# RK3399_EMMC_ADC_PCIE.net
KiCad netlist of a schematic drawn in Altium Designer
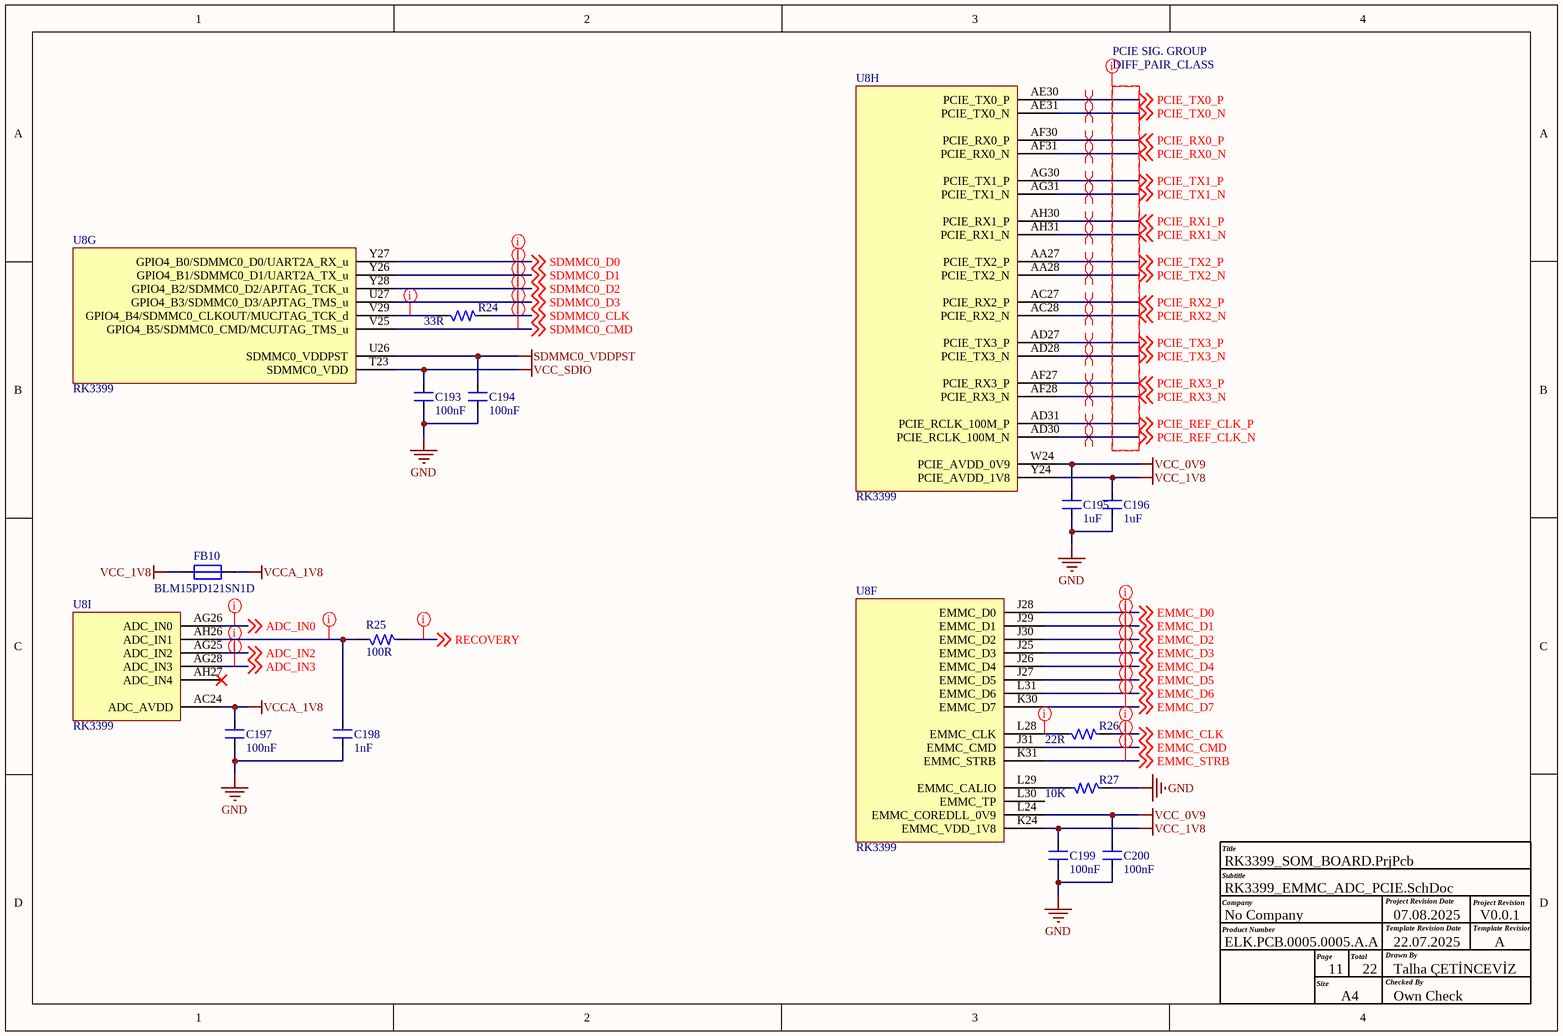
[diagram p0: RK3399_EMMC_ADC_PCIE.SchDoc]

(export (version "E")
  (design (tool "Eeschema 10.0.6"))
  (components
    (comp (ref "C193")
      (value "100nF")
      (footprint "CAP_0201")
      (description "0.1µF ±10% 25V Ceramic Capacitor X5R 0201 (0603 Metric)")
      (fields
        (field (name "MANUFACTURER") "TDK Corporation")
        (field (name "MANUFACTURER PART NUMBER") "C0603X5R1E104K030BB")
      )
      (libsource (lib "EsteemPCB_SOM_Course_intlib") (part "CAP_100nF-25V-10%-0201"))
    )
    (comp (ref "C194")
      (value "100nF")
      (footprint "CAP_0201")
      (description "0.1µF ±10% 25V Ceramic Capacitor X5R 0201 (0603 Metric)")
      (fields
        (field (name "MANUFACTURER") "TDK Corporation")
        (field (name "MANUFACTURER PART NUMBER") "C0603X5R1E104K030BB")
      )
      (libsource (lib "EsteemPCB_SOM_Course_intlib") (part "CAP_100nF-25V-10%-0201"))
    )
    (comp (ref "C195")
      (value "1uF")
      (footprint "CAP_0201")
      (description "1µF ±20% 16V Ceramic Capacitor X5R 0201 (0603 Metric)")
      (fields
        (field (name "MANUFACTURER") "Samsung Electro-Mechanics")
        (field (name "MANUFACTURER PART NUMBER") "CL03A105MO3NRNH")
      )
      (libsource (lib "EsteemPCB_SOM_Course_intlib") (part "CAP_1uF-16V-10%-0201"))
    )
    (comp (ref "C196")
      (value "1uF")
      (footprint "CAP_0201")
      (description "1µF ±20% 16V Ceramic Capacitor X5R 0201 (0603 Metric)")
      (fields
        (field (name "MANUFACTURER") "Samsung Electro-Mechanics")
        (field (name "MANUFACTURER PART NUMBER") "CL03A105MO3NRNH")
      )
      (libsource (lib "EsteemPCB_SOM_Course_intlib") (part "CAP_1uF-16V-10%-0201"))
    )
    (comp (ref "C197")
      (value "100nF")
      (footprint "CAP_0201")
      (description "0.1µF ±10% 25V Ceramic Capacitor X5R 0201 (0603 Metric)")
      (fields
        (field (name "MANUFACTURER") "TDK Corporation")
        (field (name "MANUFACTURER PART NUMBER") "C0603X5R1E104K030BB")
      )
      (libsource (lib "EsteemPCB_SOM_Course_intlib") (part "CAP_100nF-25V-10%-0201"))
    )
    (comp (ref "C198")
      (value "1nF")
      (footprint "CAP_0201")
      (description "1000pF ±10% 16V Ceramic Capacitor X7R 0201 (0603 Metric)")
      (fields
        (field (name "MANUFACTURER") "Murata Electronics")
        (field (name "MANUFACTURER PART NUMBER") "GRM033R71C102KA01D")
      )
      (libsource (lib "EsteemPCB_SOM_Course_intlib") (part "CAP_1nF-16V-10%-0201"))
    )
    (comp (ref "C199")
      (value "100nF")
      (footprint "CAP_0201")
      (description "0.1µF ±10% 25V Ceramic Capacitor X5R 0201 (0603 Metric)")
      (fields
        (field (name "MANUFACTURER") "TDK Corporation")
        (field (name "MANUFACTURER PART NUMBER") "C0603X5R1E104K030BB")
      )
      (libsource (lib "EsteemPCB_SOM_Course_intlib") (part "CAP_100nF-25V-10%-0201"))
    )
    (comp (ref "C200")
      (value "100nF")
      (footprint "CAP_0201")
      (description "0.1µF ±10% 25V Ceramic Capacitor X5R 0201 (0603 Metric)")
      (fields
        (field (name "MANUFACTURER") "TDK Corporation")
        (field (name "MANUFACTURER PART NUMBER") "C0603X5R1E104K030BB")
      )
      (libsource (lib "EsteemPCB_SOM_Course_intlib") (part "CAP_100nF-25V-10%-0201"))
    )
    (comp (ref "FB10")
      (value "BLM15PD121SN1D")
      (footprint "RES_0402")
      (description "120 Ohms @ 100MHz 1 Power Line Ferrite Bead 0402 (1005 Metric) 1.3A 90mOhm")
      (fields (field (name "MANUFACTURER") "Murata Electronics"))
      (libsource (lib "EsteemPCB_SOM_Course_intlib") (part "FB_120R-1.3A-100Mhz-0402"))
    )
    (comp (ref "R24")
      (value "33R")
      (footprint "RES_0201")
      (description "33 Ohms ±1% 0.05W, 1/20W Chip Resistor 0201 (0603 Metric) Thick Film")
      (fields
        (field (name "MANUFACTURER") "Yageo")
        (field (name "MANUFACTURER PART NUMBER") "RC0201FR-0733RL")
      )
      (libsource (lib "EsteemPCB_SOM_Course_intlib") (part "RES_33R-0.05W-1%-0201"))
    )
    (comp (ref "R25")
      (value "100R")
      (footprint "RES_0201")
      (description "100 kOhms ±1% 0.05W, 1/20W Chip Resistor 0201 (0603 Metric) Automotive AEC-Q200 Thick Film")
      (fields
        (field (name "MANUFACTURER") "Panasonic Electronic Components")
        (field (name "MANUFACTURER PART NUMBER") "ERJ-1GNF1003C")
      )
      (libsource (lib "EsteemPCB_SOM_Course_intlib") (part "RES_100R-0.05W-1%-0201"))
    )
    (comp (ref "R26")
      (value "22R")
      (footprint "RES_0201")
      (description "22 Ohms ±1% 0.05W, 1/20W Chip Resistor 0201 (0603 Metric) Moisture Resistant Thick Film")
      (fields
        (field (name "MANUFACTURER") "Yageo")
        (field (name "MANUFACTURER PART NUMBER") "RC0201FR-0722RL")
      )
      (libsource (lib "EsteemPCB_SOM_Course_intlib") (part "RES_22R-0.05W-1%-0201"))
    )
    (comp (ref "R27")
      (value "10K")
      (footprint "RES_0201")
      (description "10 kOhms ±1% 0.05W, 1/20W Chip Resistor 0201 (0603 Metric) Thick Film")
      (fields
        (field (name "MANUFACTURER") "Stackpole Electronics Inc")
        (field (name "MANUFACTURER PART NUMBER") "RMCF0201FT10K0")
      )
      (libsource (lib "EsteemPCB_SOM_Course_intlib") (part "RES_10K-0.05W-1%-0201"))
    )
    (comp (ref "U8")
      (value "RK3399")
      (footprint "FBGA828_23_826X826")
      (description "RK3399 is a low power, high performance processor for computing, personal mobile.")
      (fields (field (name "MANUFACTURER") "Rockchip"))
      (libsource (lib "EsteemPCB_SOM_Course_intlib") (part "IC_RK3399-FCBGA828"))
    )
  )
  (nets
    (net (code "1") (name "ADC_IN0") (class "Default")
      (node (ref "U8") (pin "AG26") (pinfunction "ADC_IN0_AG26") (pintype "passive"))
    )
    (net (code "2") (name "ADC_IN2") (class "Default")
      (node (ref "U8") (pin "AG25") (pinfunction "ADC_IN2_AG25") (pintype "passive"))
    )
    (net (code "3") (name "ADC_IN3") (class "Default")
      (node (ref "U8") (pin "AG28") (pinfunction "ADC_IN3_AG28") (pintype "passive"))
    )
    (net (code "4") (name "EMMC_CLK") (class "Default")
      (node (ref "R26") (pin "2") (pinfunction "2_2") (pintype "passive"))
    )
    (net (code "5") (name "EMMC_CMD") (class "Default")
      (node (ref "U8") (pin "J31") (pinfunction "EMMC_CMD_J31") (pintype "passive"))
    )
    (net (code "6") (name "EMMC_D0") (class "Default")
      (node (ref "U8") (pin "J28") (pinfunction "EMMC_D0_J28") (pintype "passive"))
    )
    (net (code "7") (name "EMMC_D1") (class "Default")
      (node (ref "U8") (pin "J29") (pinfunction "EMMC_D1_J29") (pintype "passive"))
    )
    (net (code "8") (name "EMMC_D2") (class "Default")
      (node (ref "U8") (pin "J30") (pinfunction "EMMC_D2_J30") (pintype "passive"))
    )
    (net (code "9") (name "EMMC_D3") (class "Default")
      (node (ref "U8") (pin "J25") (pinfunction "EMMC_D3_J25") (pintype "passive"))
    )
    (net (code "10") (name "EMMC_D4") (class "Default")
      (node (ref "U8") (pin "J26") (pinfunction "EMMC_D4_J26") (pintype "passive"))
    )
    (net (code "11") (name "EMMC_D5") (class "Default")
      (node (ref "U8") (pin "J27") (pinfunction "EMMC_D5_J27") (pintype "passive"))
    )
    (net (code "12") (name "EMMC_D6") (class "Default")
      (node (ref "U8") (pin "L31") (pinfunction "EMMC_D6_L31") (pintype "passive"))
    )
    (net (code "13") (name "EMMC_D7") (class "Default")
      (node (ref "U8") (pin "K30") (pinfunction "EMMC_D7_K30") (pintype "passive"))
    )
    (net (code "14") (name "EMMC_STRB") (class "Default")
      (node (ref "U8") (pin "K31") (pinfunction "EMMC_STRB_K31") (pintype "passive"))
    )
    (net (code "15") (name "GND") (class "Default")
      (node (ref "C193") (pin "1") (pinfunction "1_1") (pintype "passive"))
      (node (ref "C194") (pin "1") (pinfunction "1_1") (pintype "passive"))
      (node (ref "C195") (pin "1") (pinfunction "1_1") (pintype "passive"))
      (node (ref "C196") (pin "1") (pinfunction "1_1") (pintype "passive"))
      (node (ref "C197") (pin "1") (pinfunction "1_1") (pintype "passive"))
      (node (ref "C198") (pin "1") (pinfunction "1_1") (pintype "passive"))
      (node (ref "C199") (pin "1") (pinfunction "1_1") (pintype "passive"))
      (node (ref "C200") (pin "1") (pinfunction "1_1") (pintype "passive"))
      (node (ref "R27") (pin "1") (pinfunction "1_1") (pintype "passive"))
    )
    (net (code "16") (name "Net-(U8F-EMMC_CALIO)") (class "Default")
      (node (ref "R27") (pin "2") (pinfunction "2_2") (pintype "passive"))
      (node (ref "U8") (pin "L29") (pinfunction "EMMC_CALIO_L29") (pintype "passive"))
    )
    (net (code "17") (name "Net-(U8F-EMMC_CLK)") (class "Default")
      (node (ref "R26") (pin "1") (pinfunction "1_1") (pintype "passive"))
      (node (ref "U8") (pin "L28") (pinfunction "EMMC_CLK_L28") (pintype "passive"))
    )
    (net (code "18") (name "Net-(U8G-GPIO4_B4{slash}SDMMC0_CLKOUT{slash}MUCJTAG_TCK_d)") (class "Default")
      (node (ref "R24") (pin "1") (pinfunction "1_1") (pintype "passive"))
      (node (ref "U8") (pin "V29") (pinfunction "GPIO4_B4/SDMMC0_CLKOUT/MUCJTAG_TCK_d_V29") (pintype "passive"))
    )
    (net (code "19") (name "Net-(U8I-ADC_IN1)") (class "Default")
      (node (ref "C198") (pin "2") (pinfunction "2_2") (pintype "passive"))
      (node (ref "R25") (pin "1") (pinfunction "1_1") (pintype "passive"))
      (node (ref "U8") (pin "AH26") (pinfunction "ADC_IN1_AH26") (pintype "passive"))
    )
    (net (code "20") (name "PCIE_REF_CLK_N") (class "Default")
      (node (ref "U8") (pin "AD30") (pinfunction "PCIE_RCLK_100M_N_AD30") (pintype "passive"))
    )
    (net (code "21") (name "PCIE_REF_CLK_P") (class "Default")
      (node (ref "U8") (pin "AD31") (pinfunction "PCIE_RCLK_100M_P_AD31") (pintype "passive"))
    )
    (net (code "22") (name "PCIE_RX0_N") (class "Default")
      (node (ref "U8") (pin "AF31") (pinfunction "PCIE_RX0_N_AF31") (pintype "passive"))
    )
    (net (code "23") (name "PCIE_RX0_P") (class "Default")
      (node (ref "U8") (pin "AF30") (pinfunction "PCIE_RX0_P_AF30") (pintype "passive"))
    )
    (net (code "24") (name "PCIE_RX1_N") (class "Default")
      (node (ref "U8") (pin "AH31") (pinfunction "PCIE_RX1_N_AH31") (pintype "passive"))
    )
    (net (code "25") (name "PCIE_RX1_P") (class "Default")
      (node (ref "U8") (pin "AH30") (pinfunction "PCIE_RX1_P_AH30") (pintype "passive"))
    )
    (net (code "26") (name "PCIE_RX2_N") (class "Default")
      (node (ref "U8") (pin "AC28") (pinfunction "PCIE_RX2_N_AC28") (pintype "passive"))
    )
    (net (code "27") (name "PCIE_RX2_P") (class "Default")
      (node (ref "U8") (pin "AC27") (pinfunction "PCIE_RX2_P_AC27") (pintype "passive"))
    )
    (net (code "28") (name "PCIE_RX3_N") (class "Default")
      (node (ref "U8") (pin "AF28") (pinfunction "PCIE_RX3_N_AF28") (pintype "passive"))
    )
    (net (code "29") (name "PCIE_RX3_P") (class "Default")
      (node (ref "U8") (pin "AF27") (pinfunction "PCIE_RX3_P_AF27") (pintype "passive"))
    )
    (net (code "30") (name "PCIE_TX0_N") (class "Default")
      (node (ref "U8") (pin "AE31") (pinfunction "PCIE_TX0_N_AE31") (pintype "passive"))
    )
    (net (code "31") (name "PCIE_TX0_P") (class "Default")
      (node (ref "U8") (pin "AE30") (pinfunction "PCIE_TX0_P_AE30") (pintype "passive"))
    )
    (net (code "32") (name "PCIE_TX1_N") (class "Default")
      (node (ref "U8") (pin "AG31") (pinfunction "PCIE_TX1_N_AG31") (pintype "passive"))
    )
    (net (code "33") (name "PCIE_TX1_P") (class "Default")
      (node (ref "U8") (pin "AG30") (pinfunction "PCIE_TX1_P_AG30") (pintype "passive"))
    )
    (net (code "34") (name "PCIE_TX2_N") (class "Default")
      (node (ref "U8") (pin "AA28") (pinfunction "PCIE_TX2_N_AA28") (pintype "passive"))
    )
    (net (code "35") (name "PCIE_TX2_P") (class "Default")
      (node (ref "U8") (pin "AA27") (pinfunction "PCIE_TX2_P_AA27") (pintype "passive"))
    )
    (net (code "36") (name "PCIE_TX3_N") (class "Default")
      (node (ref "U8") (pin "AD28") (pinfunction "PCIE_TX3_N_AD28") (pintype "passive"))
    )
    (net (code "37") (name "PCIE_TX3_P") (class "Default")
      (node (ref "U8") (pin "AD27") (pinfunction "PCIE_TX3_P_AD27") (pintype "passive"))
    )
    (net (code "38") (name "RECOVERY") (class "Default")
      (node (ref "R25") (pin "2") (pinfunction "2_2") (pintype "passive"))
    )
    (net (code "39") (name "SDMMC0_CLK") (class "Default")
      (node (ref "R24") (pin "2") (pinfunction "2_2") (pintype "passive"))
    )
    (net (code "40") (name "SDMMC0_CMD") (class "Default")
      (node (ref "U8") (pin "V25") (pinfunction "GPIO4_B5/SDMMC0_CMD/MCUJTAG_TMS_u_V25") (pintype "passive"))
    )
    (net (code "41") (name "SDMMC0_D0") (class "Default")
      (node (ref "U8") (pin "Y27") (pinfunction "GPIO4_B0/SDMMC0_D0/UART2A_RX_u_Y27") (pintype "passive"))
    )
    (net (code "42") (name "SDMMC0_D1") (class "Default")
      (node (ref "U8") (pin "Y26") (pinfunction "GPIO4_B1/SDMMC0_D1/UART2A_TX_u_Y26") (pintype "passive"))
    )
    (net (code "43") (name "SDMMC0_D2") (class "Default")
      (node (ref "U8") (pin "Y28") (pinfunction "GPIO4_B2/SDMMC0_D2/APJTAG_TCK_u_Y28") (pintype "passive"))
    )
    (net (code "44") (name "SDMMC0_D3") (class "Default")
      (node (ref "U8") (pin "U27") (pinfunction "GPIO4_B3/SDMMC0_D3/APJTAG_TMS_u_U27") (pintype "passive"))
    )
    (net (code "45") (name "SDMMC0_VDDPST") (class "Default")
      (node (ref "C194") (pin "2") (pinfunction "2_2") (pintype "passive"))
      (node (ref "U8") (pin "U26") (pinfunction "SDMMC0_VDDPST_U26") (pintype "passive"))
    )
    (net (code "46") (name "VCCA_1V8") (class "Default")
      (node (ref "C197") (pin "2") (pinfunction "2_2") (pintype "passive"))
      (node (ref "FB10") (pin "2") (pinfunction "2_2") (pintype "passive"))
      (node (ref "U8") (pin "AC24") (pinfunction "ADC_AVDD_AC24") (pintype "passive"))
    )
    (net (code "47") (name "VCC_0V9") (class "Default")
      (node (ref "C195") (pin "2") (pinfunction "2_2") (pintype "passive"))
      (node (ref "C200") (pin "2") (pinfunction "2_2") (pintype "passive"))
      (node (ref "U8") (pin "L24") (pinfunction "EMMC_COREDLL_0V9_L24") (pintype "passive"))
      (node (ref "U8") (pin "W24") (pinfunction "PCIE_AVDD_0V9_W24") (pintype "passive"))
    )
    (net (code "48") (name "VCC_1V8") (class "Default")
      (node (ref "C196") (pin "2") (pinfunction "2_2") (pintype "passive"))
      (node (ref "C199") (pin "2") (pinfunction "2_2") (pintype "passive"))
      (node (ref "FB10") (pin "1") (pinfunction "1_1") (pintype "passive"))
      (node (ref "U8") (pin "K24") (pinfunction "EMMC_VDD_1V8_K24") (pintype "passive"))
      (node (ref "U8") (pin "Y24") (pinfunction "PCIE_AVDD_1V8_Y24") (pintype "passive"))
    )
    (net (code "49") (name "VCC_SDIO") (class "Default")
      (node (ref "C193") (pin "2") (pinfunction "2_2") (pintype "passive"))
      (node (ref "U8") (pin "T23") (pinfunction "SDMMC0_VDD_T23") (pintype "passive"))
    )
    (net (code "50") (name "unconnected-(U8F-EMMC_TP-PadL30)") (class "Default")
      (node (ref "U8") (pin "L30") (pinfunction "EMMC_TP_L30") (pintype "passive"))
    )
    (net (code "51") (name "unconnected-(U8I-ADC_IN4-PadAH27)") (class "Default")
      (node (ref "U8") (pin "AH27") (pinfunction "ADC_IN4_AH27") (pintype "passive+no_connect"))
    )
  )
)
